# NEpic.net
KiCad netlist of a schematic drawn in Altium Designer
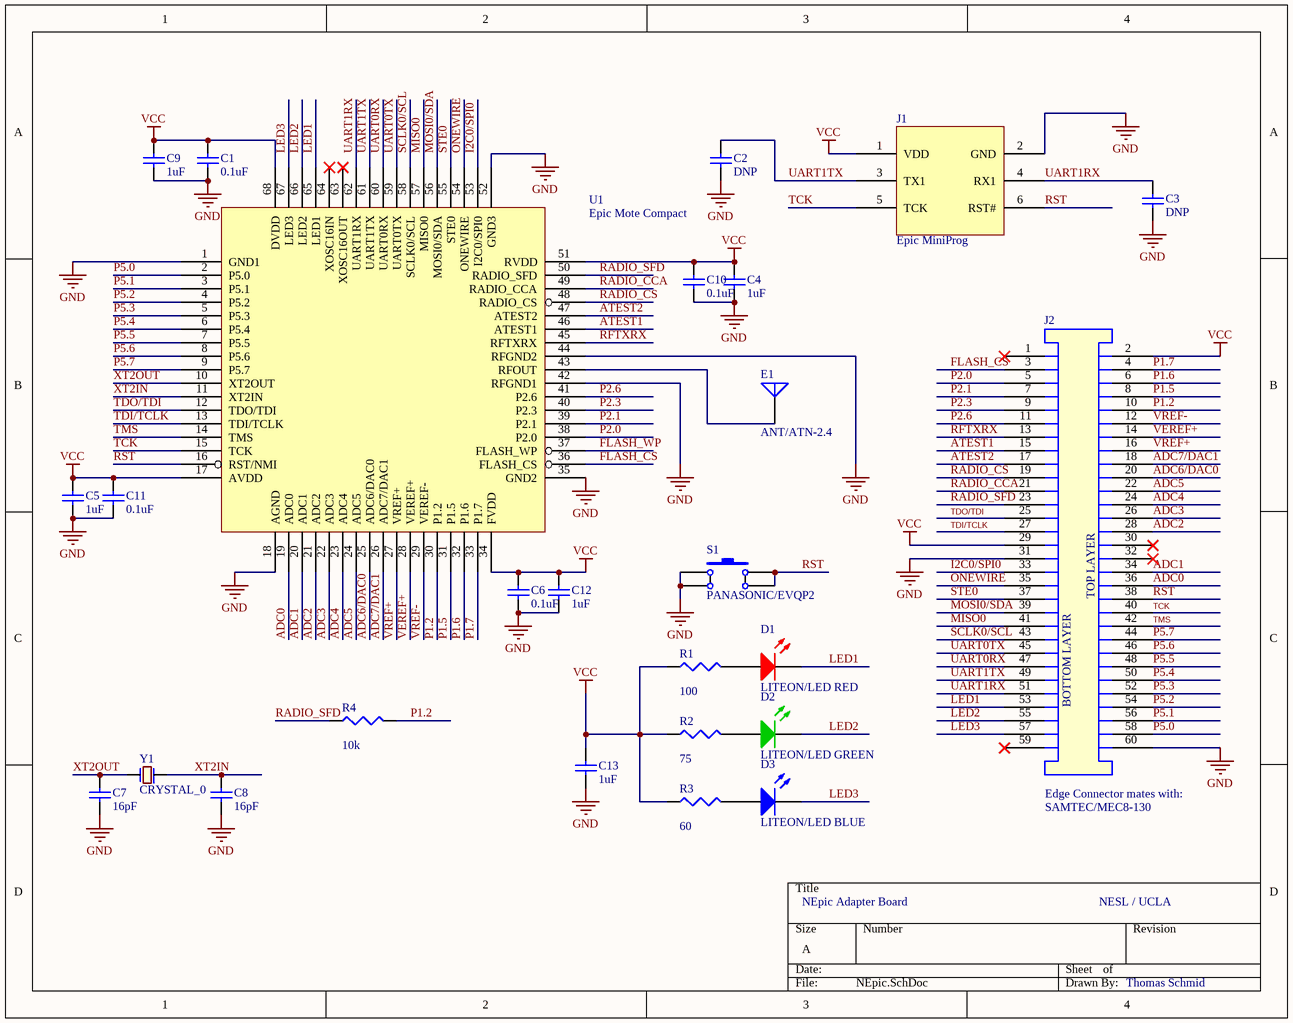
[diagram p0: NEpic.SchDoc]

(export (version "E")
  (design (tool "Eeschema 10.0.6"))
  (components
    (comp (ref "C1")
      (value "0.1uF")
      (footprint "CC1608-0603")
      (description "Capacitor (Semiconductor SIM Model)")
      (fields (field (name "Comment") "Cap") (field (name "PUBLISHER") "Altium Limited"))
      (libsource (lib "Thomas") (part "Cap"))
    )
    (comp (ref "C2")
      (value "DNP")
      (footprint "CC1608-0603")
      (description "Capacitor (Semiconductor SIM Model)")
      (fields (field (name "Comment") "Cap") (field (name "PUBLISHER") "Altium Limited"))
      (libsource (lib "Thomas") (part "Cap"))
    )
    (comp (ref "C3")
      (value "DNP")
      (footprint "CC1608-0603")
      (description "Capacitor (Semiconductor SIM Model)")
      (fields (field (name "Comment") "Cap") (field (name "PUBLISHER") "Altium Limited"))
      (libsource (lib "Thomas") (part "Cap"))
    )
    (comp (ref "C4")
      (value "1uF")
      (footprint "CC1608-0603")
      (description "Capacitor (Semiconductor SIM Model)")
      (fields (field (name "Comment") "Cap") (field (name "PUBLISHER") "Altium Limited"))
      (libsource (lib "Thomas") (part "Cap"))
    )
    (comp (ref "C5")
      (value "1uF")
      (footprint "CC1608-0603")
      (description "Capacitor (Semiconductor SIM Model)")
      (fields (field (name "Comment") "Cap") (field (name "PUBLISHER") "Altium Limited"))
      (libsource (lib "Thomas") (part "Cap"))
    )
    (comp (ref "C6")
      (value "0.1uF")
      (footprint "CC1608-0603")
      (description "Capacitor (Semiconductor SIM Model)")
      (fields (field (name "Comment") "Cap") (field (name "PUBLISHER") "Altium Limited"))
      (libsource (lib "Thomas") (part "Cap"))
    )
    (comp (ref "C7")
      (value "16pF")
      (footprint "CC1608-0603")
      (description "Capacitor (Semiconductor SIM Model)")
      (fields (field (name "Comment") "Cap") (field (name "PUBLISHER") "Altium Limited"))
      (libsource (lib "Thomas") (part "Cap"))
    )
    (comp (ref "C8")
      (value "16pF")
      (footprint "CC1608-0603")
      (description "Capacitor (Semiconductor SIM Model)")
      (fields (field (name "Comment") "Cap") (field (name "PUBLISHER") "Altium Limited"))
      (libsource (lib "Thomas") (part "Cap"))
    )
    (comp (ref "C9")
      (value "1uF")
      (footprint "CC1608-0603")
      (description "Capacitor (Semiconductor SIM Model)")
      (fields (field (name "Comment") "Cap") (field (name "PUBLISHER") "Altium Limited"))
      (libsource (lib "Thomas") (part "Cap"))
    )
    (comp (ref "C10")
      (value "0.1uF")
      (footprint "CC1608-0603")
      (description "Capacitor (Semiconductor SIM Model)")
      (fields (field (name "Comment") "Cap") (field (name "PUBLISHER") "Altium Limited"))
      (libsource (lib "Thomas") (part "Cap"))
    )
    (comp (ref "C11")
      (value "0.1uF")
      (footprint "CC1608-0603")
      (description "Capacitor (Semiconductor SIM Model)")
      (fields (field (name "Comment") "Cap") (field (name "PUBLISHER") "Altium Limited"))
      (libsource (lib "Thomas") (part "Cap"))
    )
    (comp (ref "C12")
      (value "1uF")
      (footprint "CC1608-0603")
      (description "Capacitor (Semiconductor SIM Model)")
      (fields (field (name "Comment") "Cap") (field (name "PUBLISHER") "Altium Limited"))
      (libsource (lib "Thomas") (part "Cap"))
    )
    (comp (ref "C13")
      (value "1uF")
      (footprint "CC1608-0603")
      (description "Capacitor (Semiconductor SIM Model)")
      (fields (field (name "Comment") "Cap") (field (name "PUBLISHER") "Altium Limited"))
      (libsource (lib "Thomas") (part "Cap"))
    )
    (comp (ref "D1")
      (value "LITEON/LED RED")
      (footprint "LITEON/LED/0603")
      (description "LiteOn Red LED 0605 Footprint")
      (fields (field (name "PUBLISHER") "Altium Limited"))
      (libsource (lib "Thomas") (part "LITEON/LED RED"))
    )
    (comp (ref "D2")
      (value "LITEON/LED GREEN")
      (footprint "LITEON/LED/0603")
      (description "LiteOn Green LED 0605 Footprint")
      (fields (field (name "PUBLISHER") "Altium Limited"))
      (libsource (lib "Thomas") (part "LITEON/LED GREEN"))
    )
    (comp (ref "D3")
      (value "LITEON/LED BLUE")
      (footprint "LITEON/LED/0603")
      (description "LiteOn Blue LED 0605 Footprint")
      (fields (field (name "PUBLISHER") "Altium Limited"))
      (libsource (lib "Thomas") (part "LITEON/LED BLUE"))
    )
    (comp (ref "E1")
      (value "ANT/ATN-2.4")
      (footprint "ANT/ANT-2.45-CHPCT-ND")
      (description "ANT/ANT-2.4 Chip Antenna")
      (fields (field (name "PUBLISHER") "Altium Limited"))
      (libsource (lib "Thomas") (part "Antenna"))
    )
    (comp (ref "J1")
      (value "Epic MiniProg")
      (footprint "6-pin 2mm")
      (libsource (lib "Thomas") (part "Epic MiniProg"))
    )
    (comp (ref "J2")
      (value "SAMTEC/MEC8-130")
      (footprint "SAMTEC/MEC8L-130-CARD")
      (description "0.8mm Pitch 60 pin Card Edge Socket")
      (libsource (lib "Thomas") (part "SAMTEC/HSEC8/50"))
    )
    (comp (ref "R1")
      (value "100")
      (footprint "CR1608-0603")
      (description "Resistor")
      (fields (field (name "Comment") "Res3") (field (name "PUBLISHER") "Altium Limited"))
      (libsource (lib "Miscellaneous Devices") (part "Res3"))
    )
    (comp (ref "R2")
      (value "75")
      (footprint "CR1608-0603")
      (description "Resistor")
      (fields (field (name "Comment") "Res3") (field (name "PUBLISHER") "Altium Limited"))
      (libsource (lib "Miscellaneous Devices") (part "Res3"))
    )
    (comp (ref "R3")
      (value "60")
      (footprint "CR1608-0603")
      (description "Resistor")
      (fields (field (name "Comment") "Res3") (field (name "PUBLISHER") "Altium Limited"))
      (libsource (lib "Miscellaneous Devices") (part "Res3"))
    )
    (comp (ref "R4")
      (value "10k")
      (footprint "CR1608-0603")
      (description "Resistor")
      (fields (field (name "Comment") "Res3") (field (name "PUBLISHER") "Altium Limited"))
      (libsource (lib "Miscellaneous Devices") (part "Res3"))
    )
    (comp (ref "S1")
      (value "PANASONIC/EVQP2")
      (footprint "PANASONIC/EVQP2")
      (fields (field (name "PUBLISHER") "Altium Limited"))
      (libsource (lib "Thomas") (part "PANASONIC/EVQP2"))
    )
    (comp (ref "U1")
      (value "Epic Mote Compact")
      (footprint "EPIC-Footprint")
      (libsource (lib "Thomas") (part "Epic Mote Compact"))
    )
    (comp (ref "Y1")
      (value "CRYSTAL_0")
      (footprint "FOX/FQ7050B")
      (libsource (lib "Thomas") (part "CRYSTAL_0"))
    )
  )
  (nets
    (net (code "1") (name "/ADC0") (class "Default")
      (node (ref "J2") (pin "36") (pinfunction "36_36") (pintype "passive"))
      (node (ref "U1") (pin "19") (pinfunction "ADC0_19") (pintype "passive"))
    )
    (net (code "2") (name "/ADC1") (class "Default")
      (node (ref "J2") (pin "34") (pinfunction "34_34") (pintype "passive"))
      (node (ref "U1") (pin "20") (pinfunction "ADC1_20") (pintype "passive"))
    )
    (net (code "3") (name "/ADC2") (class "Default")
      (node (ref "J2") (pin "28") (pinfunction "28_28") (pintype "passive"))
      (node (ref "U1") (pin "21") (pinfunction "ADC2_21") (pintype "passive"))
    )
    (net (code "4") (name "/ADC3") (class "Default")
      (node (ref "J2") (pin "26") (pinfunction "26_26") (pintype "passive"))
      (node (ref "U1") (pin "22") (pinfunction "ADC3_22") (pintype "passive"))
    )
    (net (code "5") (name "/ADC4") (class "Default")
      (node (ref "J2") (pin "24") (pinfunction "24_24") (pintype "passive"))
      (node (ref "U1") (pin "23") (pinfunction "ADC4_23") (pintype "passive"))
    )
    (net (code "6") (name "/ADC5") (class "Default")
      (node (ref "J2") (pin "22") (pinfunction "22_22") (pintype "passive"))
      (node (ref "U1") (pin "24") (pinfunction "ADC5_24") (pintype "passive"))
    )
    (net (code "7") (name "/ADC6{slash}DAC0") (class "Default")
      (node (ref "J2") (pin "20") (pinfunction "20_20") (pintype "passive"))
      (node (ref "U1") (pin "25") (pinfunction "ADC6/DAC0_25") (pintype "passive"))
    )
    (net (code "8") (name "/ADC7{slash}DAC1") (class "Default")
      (node (ref "J2") (pin "18") (pinfunction "18_18") (pintype "passive"))
      (node (ref "U1") (pin "26") (pinfunction "ADC7/DAC1_26") (pintype "passive"))
    )
    (net (code "9") (name "/ATEST1") (class "Default")
      (node (ref "J2") (pin "15") (pinfunction "15_15") (pintype "passive"))
      (node (ref "U1") (pin "46") (pinfunction "ATEST1_46") (pintype "passive"))
    )
    (net (code "10") (name "/ATEST2") (class "Default")
      (node (ref "J2") (pin "17") (pinfunction "17_17") (pintype "passive"))
      (node (ref "U1") (pin "47") (pinfunction "ATEST2_47") (pintype "passive"))
    )
    (net (code "11") (name "/FLASH_CS") (class "Default")
      (node (ref "J2") (pin "3") (pinfunction "3_3") (pintype "passive"))
      (node (ref "U1") (pin "36") (pinfunction "FLASH_CS_36") (pintype "passive"))
    )
    (net (code "12") (name "/FLASH_WP") (class "Default")
      (node (ref "U1") (pin "37") (pinfunction "FLASH_WP_37") (pintype "passive"))
    )
    (net (code "13") (name "/I2C0{slash}SPI0") (class "Default")
      (node (ref "J2") (pin "33") (pinfunction "33_33") (pintype "passive"))
      (node (ref "U1") (pin "53") (pinfunction "I2C0/SPI0_53") (pintype "passive"))
    )
    (net (code "14") (name "/LED1") (class "Default")
      (node (ref "D1") (pin "2") (pinfunction "K_2") (pintype "passive"))
      (node (ref "J2") (pin "53") (pinfunction "53_53") (pintype "passive"))
      (node (ref "U1") (pin "65") (pinfunction "LED1_65") (pintype "passive"))
    )
    (net (code "15") (name "/LED2") (class "Default")
      (node (ref "D2") (pin "2") (pinfunction "K_2") (pintype "passive"))
      (node (ref "J2") (pin "55") (pinfunction "55_55") (pintype "passive"))
      (node (ref "U1") (pin "66") (pinfunction "LED2_66") (pintype "passive"))
    )
    (net (code "16") (name "/LED3") (class "Default")
      (node (ref "D3") (pin "2") (pinfunction "K_2") (pintype "passive"))
      (node (ref "J2") (pin "57") (pinfunction "57_57") (pintype "passive"))
      (node (ref "U1") (pin "67") (pinfunction "LED3_67") (pintype "passive"))
    )
    (net (code "17") (name "/MISO0") (class "Default")
      (node (ref "J2") (pin "41") (pinfunction "41_41") (pintype "passive"))
      (node (ref "U1") (pin "57") (pinfunction "MISO0_57") (pintype "passive"))
    )
    (net (code "18") (name "/MOSI0{slash}SDA") (class "Default")
      (node (ref "J2") (pin "39") (pinfunction "39_39") (pintype "passive"))
      (node (ref "U1") (pin "56") (pinfunction "MOSI0/SDA_56") (pintype "passive"))
    )
    (net (code "19") (name "/ONEWIRE") (class "Default")
      (node (ref "J2") (pin "35") (pinfunction "35_35") (pintype "passive"))
      (node (ref "U1") (pin "54") (pinfunction "ONEWIRE_54") (pintype "passive"))
    )
    (net (code "20") (name "/P1.2") (class "Default")
      (node (ref "J2") (pin "10") (pinfunction "10_10") (pintype "passive"))
      (node (ref "R4") (pin "2") (pinfunction "2_2") (pintype "passive"))
      (node (ref "U1") (pin "30") (pinfunction "P1.2_30") (pintype "passive"))
    )
    (net (code "21") (name "/P1.5") (class "Default")
      (node (ref "J2") (pin "8") (pinfunction "8_8") (pintype "passive"))
      (node (ref "U1") (pin "31") (pinfunction "P1.5_31") (pintype "passive"))
    )
    (net (code "22") (name "/P1.6") (class "Default")
      (node (ref "J2") (pin "6") (pinfunction "6_6") (pintype "passive"))
      (node (ref "U1") (pin "32") (pinfunction "P1.6_32") (pintype "passive"))
    )
    (net (code "23") (name "/P1.7") (class "Default")
      (node (ref "J2") (pin "4") (pinfunction "4_4") (pintype "passive"))
      (node (ref "U1") (pin "33") (pinfunction "P1.7_33") (pintype "passive"))
    )
    (net (code "24") (name "/P2.0") (class "Default")
      (node (ref "J2") (pin "5") (pinfunction "5_5") (pintype "passive"))
      (node (ref "U1") (pin "38") (pinfunction "P2.0_38") (pintype "passive"))
    )
    (net (code "25") (name "/P2.1") (class "Default")
      (node (ref "J2") (pin "7") (pinfunction "7_7") (pintype "passive"))
      (node (ref "U1") (pin "39") (pinfunction "P2.1_39") (pintype "passive"))
    )
    (net (code "26") (name "/P2.3") (class "Default")
      (node (ref "J2") (pin "9") (pinfunction "9_9") (pintype "passive"))
      (node (ref "U1") (pin "40") (pinfunction "P2.3_40") (pintype "passive"))
    )
    (net (code "27") (name "/P2.6") (class "Default")
      (node (ref "J2") (pin "11") (pinfunction "11_11") (pintype "passive"))
      (node (ref "U1") (pin "41") (pinfunction "P2.6_41") (pintype "passive"))
    )
    (net (code "28") (name "/P5.0") (class "Default")
      (node (ref "J2") (pin "58") (pinfunction "58_58") (pintype "passive"))
      (node (ref "U1") (pin "2") (pinfunction "P5.0_2") (pintype "passive"))
    )
    (net (code "29") (name "/P5.1") (class "Default")
      (node (ref "J2") (pin "56") (pinfunction "56_56") (pintype "passive"))
      (node (ref "U1") (pin "3") (pinfunction "P5.1_3") (pintype "passive"))
    )
    (net (code "30") (name "/P5.2") (class "Default")
      (node (ref "J2") (pin "54") (pinfunction "54_54") (pintype "passive"))
      (node (ref "U1") (pin "4") (pinfunction "P5.2_4") (pintype "passive"))
    )
    (net (code "31") (name "/P5.3") (class "Default")
      (node (ref "J2") (pin "52") (pinfunction "52_52") (pintype "passive"))
      (node (ref "U1") (pin "5") (pinfunction "P5.3_5") (pintype "passive"))
    )
    (net (code "32") (name "/P5.4") (class "Default")
      (node (ref "J2") (pin "50") (pinfunction "50_50") (pintype "passive"))
      (node (ref "U1") (pin "6") (pinfunction "P5.4_6") (pintype "passive"))
    )
    (net (code "33") (name "/P5.5") (class "Default")
      (node (ref "J2") (pin "48") (pinfunction "48_48") (pintype "passive"))
      (node (ref "U1") (pin "7") (pinfunction "P5.5_7") (pintype "passive"))
    )
    (net (code "34") (name "/P5.6") (class "Default")
      (node (ref "J2") (pin "46") (pinfunction "46_46") (pintype "passive"))
      (node (ref "U1") (pin "8") (pinfunction "P5.6_8") (pintype "passive"))
    )
    (net (code "35") (name "/P5.7") (class "Default")
      (node (ref "J2") (pin "44") (pinfunction "44_44") (pintype "passive"))
      (node (ref "U1") (pin "9") (pinfunction "P5.7_9") (pintype "passive"))
    )
    (net (code "36") (name "/RADIO_CCA") (class "Default")
      (node (ref "J2") (pin "21") (pinfunction "21_21") (pintype "passive"))
      (node (ref "U1") (pin "49") (pinfunction "RADIO_CCA_49") (pintype "passive"))
    )
    (net (code "37") (name "/RADIO_CS") (class "Default")
      (node (ref "J2") (pin "19") (pinfunction "19_19") (pintype "passive"))
      (node (ref "U1") (pin "48") (pinfunction "RADIO_CS_48") (pintype "passive"))
    )
    (net (code "38") (name "/RADIO_SFD") (class "Default")
      (node (ref "J2") (pin "23") (pinfunction "23_23") (pintype "passive"))
      (node (ref "R4") (pin "1") (pinfunction "1_1") (pintype "passive"))
      (node (ref "U1") (pin "50") (pinfunction "RADIO_SFD_50") (pintype "passive"))
    )
    (net (code "39") (name "/RFTXRX") (class "Default")
      (node (ref "J2") (pin "13") (pinfunction "13_13") (pintype "passive"))
      (node (ref "U1") (pin "45") (pinfunction "RFTXRX_45") (pintype "passive"))
    )
    (net (code "40") (name "/RST") (class "Default")
      (node (ref "J1") (pin "6") (pinfunction "RST#_6") (pintype "passive"))
      (node (ref "J2") (pin "38") (pinfunction "38_38") (pintype "passive"))
      (node (ref "S1") (pin "2") (pinfunction "2_2") (pintype "passive"))
      (node (ref "S1") (pin "4") (pinfunction "4_4") (pintype "passive"))
      (node (ref "U1") (pin "16") (pinfunction "RST/NMI_16") (pintype "passive"))
    )
    (net (code "41") (name "/SCLK0{slash}SCL") (class "Default")
      (node (ref "J2") (pin "43") (pinfunction "43_43") (pintype "passive"))
      (node (ref "U1") (pin "58") (pinfunction "SCLK0/SCL_58") (pintype "passive"))
    )
    (net (code "42") (name "/STE0") (class "Default")
      (node (ref "J2") (pin "37") (pinfunction "37_37") (pintype "passive"))
      (node (ref "U1") (pin "55") (pinfunction "STE0_55") (pintype "passive"))
    )
    (net (code "43") (name "/TCK") (class "Default")
      (node (ref "J1") (pin "5") (pinfunction "TCK_5") (pintype "passive"))
      (node (ref "J2") (pin "40") (pinfunction "40_40") (pintype "passive"))
      (node (ref "U1") (pin "15") (pinfunction "TCK_15") (pintype "passive"))
    )
    (net (code "44") (name "/TDI{slash}TCLK") (class "Default")
      (node (ref "J2") (pin "27") (pinfunction "27_27") (pintype "passive"))
      (node (ref "U1") (pin "13") (pinfunction "TDI/TCLK_13") (pintype "passive"))
    )
    (net (code "45") (name "/TDO{slash}TDI") (class "Default")
      (node (ref "J2") (pin "25") (pinfunction "25_25") (pintype "passive"))
      (node (ref "U1") (pin "12") (pinfunction "TDO/TDI_12") (pintype "passive"))
    )
    (net (code "46") (name "/TMS") (class "Default")
      (node (ref "J2") (pin "42") (pinfunction "42_42") (pintype "passive"))
      (node (ref "U1") (pin "14") (pinfunction "TMS_14") (pintype "passive"))
    )
    (net (code "47") (name "/UART0RX") (class "Default")
      (node (ref "J2") (pin "47") (pinfunction "47_47") (pintype "passive"))
      (node (ref "U1") (pin "60") (pinfunction "UART0RX_60") (pintype "passive"))
    )
    (net (code "48") (name "/UART0TX") (class "Default")
      (node (ref "J2") (pin "45") (pinfunction "45_45") (pintype "passive"))
      (node (ref "U1") (pin "59") (pinfunction "UART0TX_59") (pintype "passive"))
    )
    (net (code "49") (name "/UART1RX") (class "Default")
      (node (ref "C3") (pin "2") (pinfunction "2_2") (pintype "passive"))
      (node (ref "J1") (pin "4") (pinfunction "RX1_4") (pintype "passive"))
      (node (ref "J2") (pin "51") (pinfunction "51_51") (pintype "passive"))
      (node (ref "U1") (pin "62") (pinfunction "UART1RX_62") (pintype "passive"))
    )
    (net (code "50") (name "/UART1TX") (class "Default")
      (node (ref "C2") (pin "2") (pinfunction "2_2") (pintype "passive"))
      (node (ref "J1") (pin "3") (pinfunction "TX1_3") (pintype "passive"))
      (node (ref "J2") (pin "49") (pinfunction "49_49") (pintype "passive"))
      (node (ref "U1") (pin "61") (pinfunction "UART1TX_61") (pintype "passive"))
    )
    (net (code "51") (name "/VEREF+") (class "Default")
      (node (ref "J2") (pin "14") (pinfunction "14_14") (pintype "passive"))
      (node (ref "U1") (pin "28") (pinfunction "VEREF+_28") (pintype "passive"))
    )
    (net (code "52") (name "/VREF+") (class "Default")
      (node (ref "J2") (pin "16") (pinfunction "16_16") (pintype "passive"))
      (node (ref "U1") (pin "27") (pinfunction "VREF+_27") (pintype "passive"))
    )
    (net (code "53") (name "/VREF-") (class "Default")
      (node (ref "J2") (pin "12") (pinfunction "12_12") (pintype "passive"))
      (node (ref "U1") (pin "29") (pinfunction "VEREF-_29") (pintype "passive"))
    )
    (net (code "54") (name "/XT2IN") (class "Default")
      (node (ref "C8") (pin "2") (pinfunction "2_2") (pintype "passive"))
      (node (ref "U1") (pin "11") (pinfunction "XT2IN_11") (pintype "passive"))
      (node (ref "Y1") (pin "2") (pinfunction "2_2") (pintype "passive"))
    )
    (net (code "55") (name "/XT2OUT") (class "Default")
      (node (ref "C7") (pin "2") (pinfunction "2_2") (pintype "passive"))
      (node (ref "U1") (pin "10") (pinfunction "XT2OUT_10") (pintype "passive"))
      (node (ref "Y1") (pin "1") (pinfunction "1_1") (pintype "passive"))
    )
    (net (code "56") (name "GND") (class "Default")
      (node (ref "C1") (pin "1") (pinfunction "1_1") (pintype "passive"))
      (node (ref "C10") (pin "1") (pinfunction "1_1") (pintype "passive"))
      (node (ref "C11") (pin "1") (pinfunction "1_1") (pintype "passive"))
      (node (ref "C12") (pin "1") (pinfunction "1_1") (pintype "passive"))
      (node (ref "C13") (pin "1") (pinfunction "1_1") (pintype "passive"))
      (node (ref "C2") (pin "1") (pinfunction "1_1") (pintype "passive"))
      (node (ref "C3") (pin "1") (pinfunction "1_1") (pintype "passive"))
      (node (ref "C4") (pin "1") (pinfunction "1_1") (pintype "passive"))
      (node (ref "C5") (pin "1") (pinfunction "1_1") (pintype "passive"))
      (node (ref "C6") (pin "1") (pinfunction "1_1") (pintype "passive"))
      (node (ref "C7") (pin "1") (pinfunction "1_1") (pintype "passive"))
      (node (ref "C8") (pin "1") (pinfunction "1_1") (pintype "passive"))
      (node (ref "C9") (pin "1") (pinfunction "1_1") (pintype "passive"))
      (node (ref "J1") (pin "2") (pinfunction "GND_2") (pintype "passive"))
      (node (ref "J2") (pin "31") (pinfunction "31_31") (pintype "passive"))
      (node (ref "J2") (pin "60") (pinfunction "60_60") (pintype "passive"))
      (node (ref "S1") (pin "1") (pinfunction "1_1") (pintype "passive"))
      (node (ref "S1") (pin "3") (pinfunction "3_3") (pintype "passive"))
      (node (ref "U1") (pin "1") (pinfunction "GND1_1") (pintype "passive"))
      (node (ref "U1") (pin "18") (pinfunction "AGND_18") (pintype "passive"))
      (node (ref "U1") (pin "35") (pinfunction "GND2_35") (pintype "passive"))
      (node (ref "U1") (pin "42") (pinfunction "RFGND1_42") (pintype "passive"))
      (node (ref "U1") (pin "44") (pinfunction "RFGND2_44") (pintype "passive"))
      (node (ref "U1") (pin "52") (pinfunction "GND3_52") (pintype "passive"))
    )
    (net (code "57") (name "Net-(D1-A)") (class "Default")
      (node (ref "D1") (pin "1") (pinfunction "A_1") (pintype "passive"))
      (node (ref "R1") (pin "2") (pinfunction "2_2") (pintype "passive"))
    )
    (net (code "58") (name "Net-(D2-A)") (class "Default")
      (node (ref "D2") (pin "1") (pinfunction "A_1") (pintype "passive"))
      (node (ref "R2") (pin "2") (pinfunction "2_2") (pintype "passive"))
    )
    (net (code "59") (name "Net-(D3-A)") (class "Default")
      (node (ref "D3") (pin "1") (pinfunction "A_1") (pintype "passive"))
      (node (ref "R3") (pin "2") (pinfunction "2_2") (pintype "passive"))
    )
    (net (code "60") (name "Net-(E1-A)") (class "Default")
      (node (ref "E1") (pin "1") (pinfunction "A_1") (pintype "passive"))
      (node (ref "U1") (pin "43") (pinfunction "RFOUT_43") (pintype "passive"))
    )
    (net (code "61") (name "VCC") (class "Default")
      (node (ref "C1") (pin "2") (pinfunction "2_2") (pintype "passive"))
      (node (ref "C10") (pin "2") (pinfunction "2_2") (pintype "passive"))
      (node (ref "C11") (pin "2") (pinfunction "2_2") (pintype "passive"))
      (node (ref "C12") (pin "2") (pinfunction "2_2") (pintype "passive"))
      (node (ref "C13") (pin "2") (pinfunction "2_2") (pintype "passive"))
      (node (ref "C4") (pin "2") (pinfunction "2_2") (pintype "passive"))
      (node (ref "C5") (pin "2") (pinfunction "2_2") (pintype "passive"))
      (node (ref "C6") (pin "2") (pinfunction "2_2") (pintype "passive"))
      (node (ref "C9") (pin "2") (pinfunction "2_2") (pintype "passive"))
      (node (ref "J1") (pin "1") (pinfunction "VDD_1") (pintype "passive"))
      (node (ref "J2") (pin "2") (pinfunction "2_2") (pintype "passive"))
      (node (ref "J2") (pin "29") (pinfunction "29_29") (pintype "passive"))
      (node (ref "R1") (pin "1") (pinfunction "1_1") (pintype "passive"))
      (node (ref "R2") (pin "1") (pinfunction "1_1") (pintype "passive"))
      (node (ref "R3") (pin "1") (pinfunction "1_1") (pintype "passive"))
      (node (ref "U1") (pin "17") (pinfunction "AVDD_17") (pintype "passive"))
      (node (ref "U1") (pin "34") (pinfunction "FVDD_34") (pintype "passive"))
      (node (ref "U1") (pin "51") (pinfunction "RVDD_51") (pintype "passive"))
      (node (ref "U1") (pin "68") (pinfunction "DVDD_68") (pintype "passive"))
    )
    (net (code "62") (name "unconnected-(J2-Pad1)") (class "Default")
      (node (ref "J2") (pin "1") (pinfunction "1_1") (pintype "passive+no_connect"))
    )
    (net (code "63") (name "unconnected-(J2-Pad30)") (class "Default")
      (node (ref "J2") (pin "30") (pinfunction "30_30") (pintype "passive+no_connect"))
    )
    (net (code "64") (name "unconnected-(J2-Pad32)") (class "Default")
      (node (ref "J2") (pin "32") (pinfunction "32_32") (pintype "passive+no_connect"))
    )
    (net (code "65") (name "unconnected-(J2-Pad59)") (class "Default")
      (node (ref "J2") (pin "59") (pinfunction "59_59") (pintype "passive+no_connect"))
    )
    (net (code "66") (name "unconnected-(U1-XOSC16IN-Pad64)") (class "Default")
      (node (ref "U1") (pin "64") (pinfunction "XOSC16IN_64") (pintype "passive+no_connect"))
    )
    (net (code "67") (name "unconnected-(U1-XOSC16OUT-Pad63)") (class "Default")
      (node (ref "U1") (pin "63") (pinfunction "XOSC16OUT_63") (pintype "passive+no_connect"))
    )
  )
)
